# synth-zodiac-scorpio-kbd.net
KiCad netlist of a schematic drawn in EAGLE
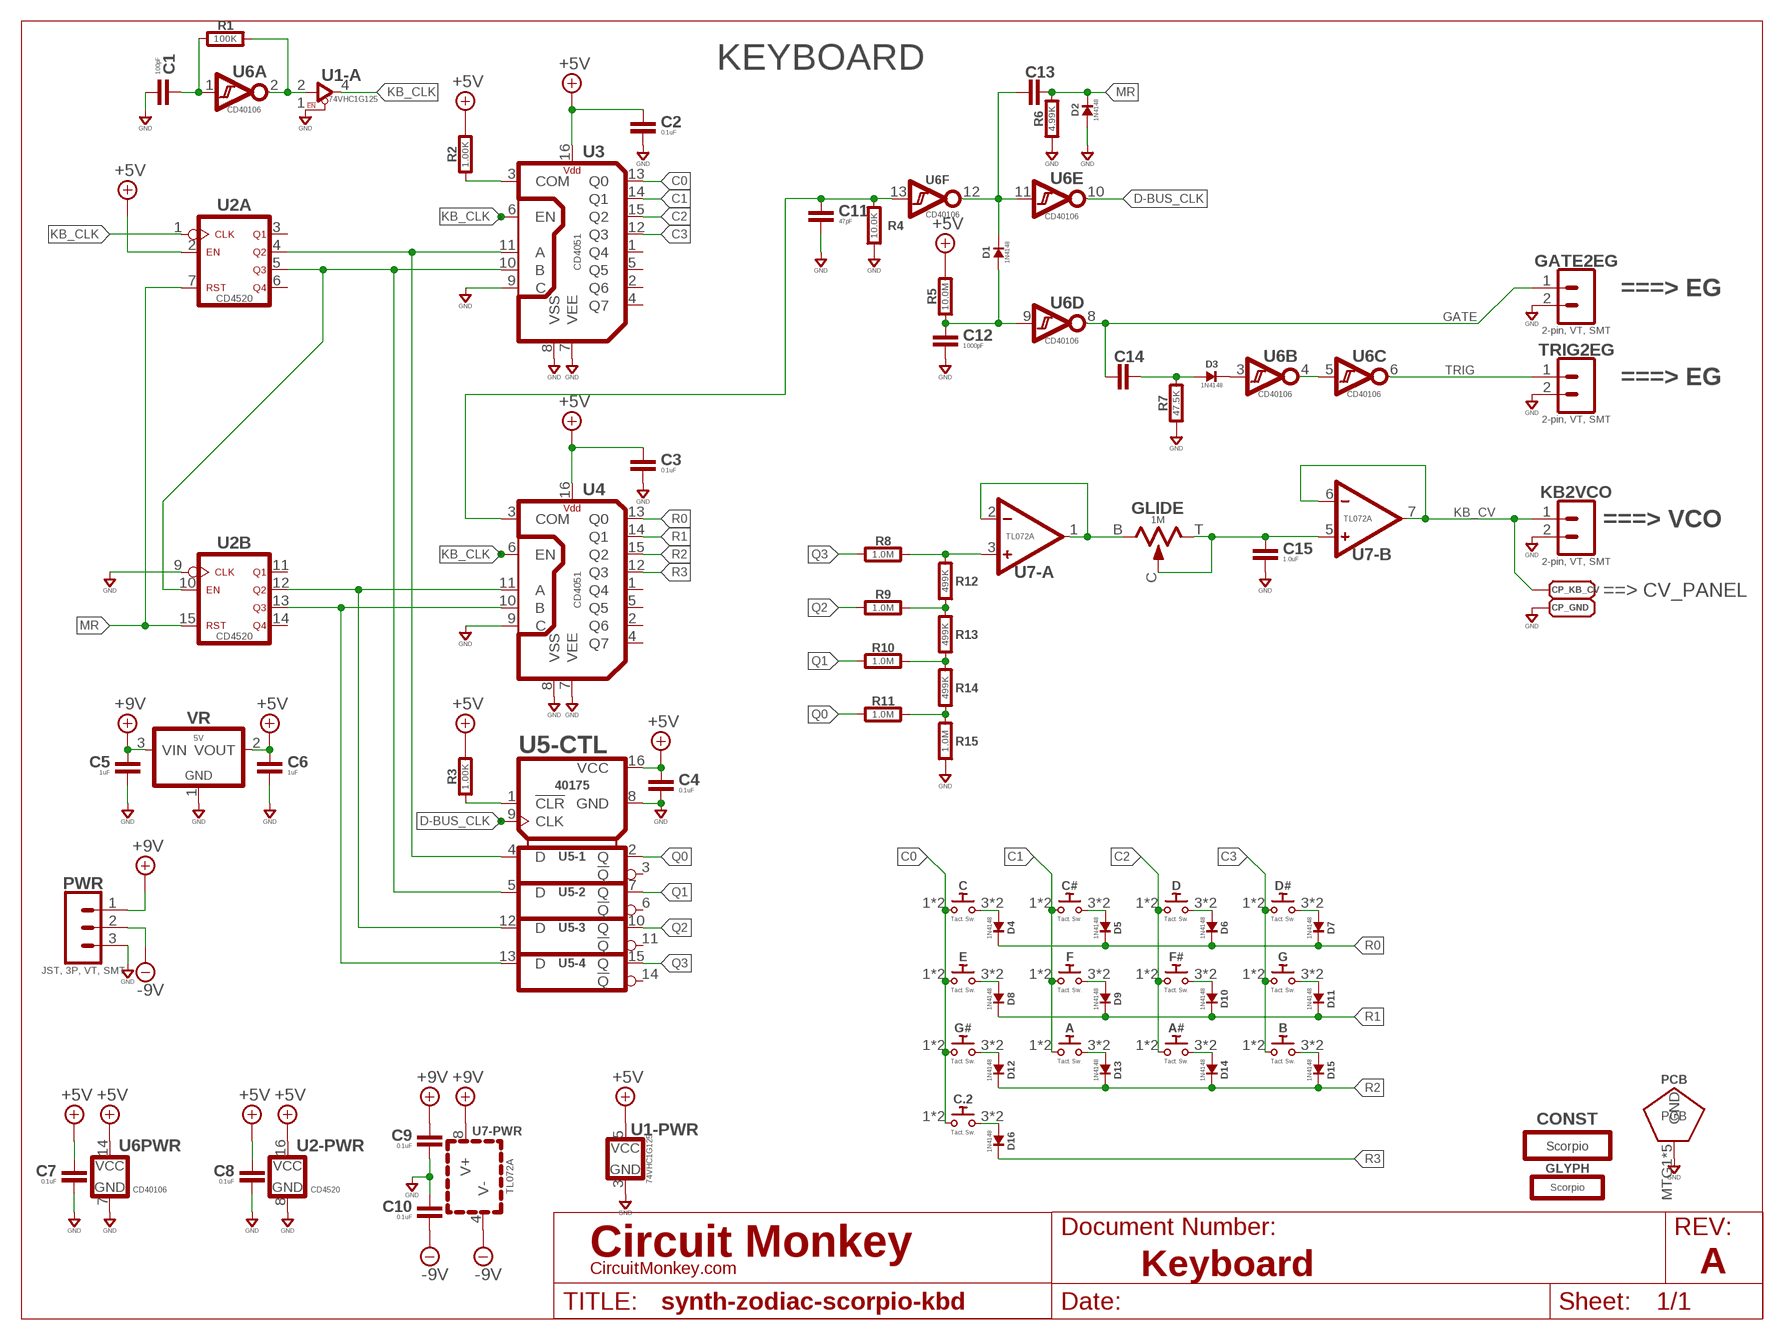
[diagram p0: schematic, sheet 1]

(export (version "E")
  (design (tool "Eeschema 10.0.6"))
  (components
    (comp (ref "A")
      (value "Tact. Sw.")
      (footprint "eagle-import:B3FS")
      (fields (field (name "MFR") "Omron") (field (name "MPN") "B3FS-10*"))
      (libsource (lib "eagle-import") (part "PUSHBTN-MOMB3FS"))
    )
    (comp (ref "A#")
      (value "Tact. Sw.")
      (footprint "eagle-import:B3FS")
      (fields (field (name "MFR") "Omron") (field (name "MPN") "B3FS-10*"))
      (libsource (lib "eagle-import") (part "PUSHBTN-MOMB3FS"))
    )
    (comp (ref "B")
      (value "Tact. Sw.")
      (footprint "eagle-import:B3FS")
      (fields (field (name "MFR") "Omron") (field (name "MPN") "B3FS-10*"))
      (libsource (lib "eagle-import") (part "PUSHBTN-MOMB3FS"))
    )
    (comp (ref "C")
      (value "Tact. Sw.")
      (footprint "eagle-import:B3FS")
      (fields (field (name "MFR") "Omron") (field (name "MPN") "B3FS-10*"))
      (libsource (lib "eagle-import") (part "PUSHBTN-MOMB3FS"))
    )
    (comp (ref "C#")
      (value "Tact. Sw.")
      (footprint "eagle-import:B3FS")
      (fields (field (name "MFR") "Omron") (field (name "MPN") "B3FS-10*"))
      (libsource (lib "eagle-import") (part "PUSHBTN-MOMB3FS"))
    )
    (comp (ref "C.2")
      (value "Tact. Sw.")
      (footprint "eagle-import:B3FS")
      (fields (field (name "MFR") "Omron") (field (name "MPN") "B3FS-10*"))
      (libsource (lib "eagle-import") (part "PUSHBTN-MOMB3FS"))
    )
    (comp (ref "C1")
      (value "100pF")
      (footprint "eagle-import:0603-CAP")
      (libsource (lib "eagle-import") (part "CAPACITOR0603"))
    )
    (comp (ref "C2")
      (value "0.1uF")
      (footprint "eagle-import:0603-CAP")
      (libsource (lib "eagle-import") (part "CAPACITOR0603"))
    )
    (comp (ref "C3")
      (value "0.1uF")
      (footprint "eagle-import:0603-CAP")
      (libsource (lib "eagle-import") (part "CAPACITOR0603"))
    )
    (comp (ref "C4")
      (value "0.1uF")
      (footprint "eagle-import:0603-CAP")
      (libsource (lib "eagle-import") (part "CAPACITOR0603"))
    )
    (comp (ref "C5")
      (value "1uF")
      (footprint "eagle-import:0603-CAP")
      (libsource (lib "eagle-import") (part "CAPACITOR0603"))
    )
    (comp (ref "C6")
      (value "1uF")
      (footprint "eagle-import:0603-CAP")
      (libsource (lib "eagle-import") (part "CAPACITOR0603"))
    )
    (comp (ref "C7")
      (value "0.1uF")
      (footprint "eagle-import:0603-CAP")
      (libsource (lib "eagle-import") (part "CAPACITOR0603"))
    )
    (comp (ref "C8")
      (value "0.1uF")
      (footprint "eagle-import:0603-CAP")
      (libsource (lib "eagle-import") (part "CAPACITOR0603"))
    )
    (comp (ref "C9")
      (value "0.1uF")
      (footprint "eagle-import:0603-CAP")
      (libsource (lib "eagle-import") (part "CAPACITOR0603"))
    )
    (comp (ref "C10")
      (value "0.1uF")
      (footprint "eagle-import:0603-CAP")
      (libsource (lib "eagle-import") (part "CAPACITOR0603"))
    )
    (comp (ref "C11")
      (value "47pF")
      (footprint "eagle-import:0603-CAP")
      (libsource (lib "eagle-import") (part "CAPACITOR0603"))
    )
    (comp (ref "C12")
      (value "1000pF")
      (footprint "eagle-import:0603-CAP")
      (libsource (lib "eagle-import") (part "CAPACITOR0603"))
    )
    (comp (ref "C13")
      (value "220pF")
      (footprint "eagle-import:0603-CAP")
      (libsource (lib "eagle-import") (part "CAPACITOR0603"))
    )
    (comp (ref "C14")
      (value "0.1uF")
      (footprint "eagle-import:0603-CAP")
      (libsource (lib "eagle-import") (part "CAPACITOR0603"))
    )
    (comp (ref "C15")
      (value "1.0uF")
      (footprint "eagle-import:0603-CAP")
      (libsource (lib "eagle-import") (part "CAPACITOR0603"))
    )
    (comp (ref "CONST")
      (value "Scorpio")
      (footprint "eagle-import:SCORPIO-CONST")
      (libsource (lib "eagle-import") (part "CONSTELLATION-SCORPIO"))
    )
    (comp (ref "CP_GND")
      (value "PAD-70X70SMD-070X070")
      (footprint "eagle-import:SMD-070MIL")
      (libsource (lib "eagle-import") (part "PAD-70X70SMD-070X070"))
    )
    (comp (ref "CP_KB_CV")
      (value "PAD-70X70SMD-070X070")
      (footprint "eagle-import:SMD-070MIL")
      (libsource (lib "eagle-import") (part "PAD-70X70SMD-070X070"))
    )
    (comp (ref "D")
      (value "Tact. Sw.")
      (footprint "eagle-import:B3FS")
      (fields (field (name "MFR") "Omron") (field (name "MPN") "B3FS-10*"))
      (libsource (lib "eagle-import") (part "PUSHBTN-MOMB3FS"))
    )
    (comp (ref "D#")
      (value "Tact. Sw.")
      (footprint "eagle-import:B3FS")
      (fields (field (name "MFR") "Omron") (field (name "MPN") "B3FS-10*"))
      (libsource (lib "eagle-import") (part "PUSHBTN-MOMB3FS"))
    )
    (comp (ref "D1")
      (value "1N4148")
      (footprint "eagle-import:SOD-123")
      (fields (field (name "MPN") "1N4148W"))
      (libsource (lib "eagle-import") (part "DIODE-1N4148"))
    )
    (comp (ref "D2")
      (value "1N4148")
      (footprint "eagle-import:SOD-123")
      (fields (field (name "MPN") "1N4148W"))
      (libsource (lib "eagle-import") (part "DIODE-1N4148"))
    )
    (comp (ref "D3")
      (value "1N4148")
      (footprint "eagle-import:SOD-123")
      (fields (field (name "MPN") "1N4148W"))
      (libsource (lib "eagle-import") (part "DIODE-1N4148"))
    )
    (comp (ref "D4")
      (value "1N4148")
      (footprint "eagle-import:SOD-123")
      (fields (field (name "MPN") "1N4148W"))
      (libsource (lib "eagle-import") (part "DIODE-1N4148"))
    )
    (comp (ref "D5")
      (value "1N4148")
      (footprint "eagle-import:SOD-123")
      (fields (field (name "MPN") "1N4148W"))
      (libsource (lib "eagle-import") (part "DIODE-1N4148"))
    )
    (comp (ref "D6")
      (value "1N4148")
      (footprint "eagle-import:SOD-123")
      (fields (field (name "MPN") "1N4148W"))
      (libsource (lib "eagle-import") (part "DIODE-1N4148"))
    )
    (comp (ref "D7")
      (value "1N4148")
      (footprint "eagle-import:SOD-123")
      (fields (field (name "MPN") "1N4148W"))
      (libsource (lib "eagle-import") (part "DIODE-1N4148"))
    )
    (comp (ref "D8")
      (value "1N4148")
      (footprint "eagle-import:SOD-123")
      (fields (field (name "MPN") "1N4148W"))
      (libsource (lib "eagle-import") (part "DIODE-1N4148"))
    )
    (comp (ref "D9")
      (value "1N4148")
      (footprint "eagle-import:SOD-123")
      (fields (field (name "MPN") "1N4148W"))
      (libsource (lib "eagle-import") (part "DIODE-1N4148"))
    )
    (comp (ref "D10")
      (value "1N4148")
      (footprint "eagle-import:SOD-123")
      (fields (field (name "MPN") "1N4148W"))
      (libsource (lib "eagle-import") (part "DIODE-1N4148"))
    )
    (comp (ref "D11")
      (value "1N4148")
      (footprint "eagle-import:SOD-123")
      (fields (field (name "MPN") "1N4148W"))
      (libsource (lib "eagle-import") (part "DIODE-1N4148"))
    )
    (comp (ref "D12")
      (value "1N4148")
      (footprint "eagle-import:SOD-123")
      (fields (field (name "MPN") "1N4148W"))
      (libsource (lib "eagle-import") (part "DIODE-1N4148"))
    )
    (comp (ref "D13")
      (value "1N4148")
      (footprint "eagle-import:SOD-123")
      (fields (field (name "MPN") "1N4148W"))
      (libsource (lib "eagle-import") (part "DIODE-1N4148"))
    )
    (comp (ref "D14")
      (value "1N4148")
      (footprint "eagle-import:SOD-123")
      (fields (field (name "MPN") "1N4148W"))
      (libsource (lib "eagle-import") (part "DIODE-1N4148"))
    )
    (comp (ref "D15")
      (value "1N4148")
      (footprint "eagle-import:SOD-123")
      (fields (field (name "MPN") "1N4148W"))
      (libsource (lib "eagle-import") (part "DIODE-1N4148"))
    )
    (comp (ref "D16")
      (value "1N4148")
      (footprint "eagle-import:SOD-123")
      (fields (field (name "MPN") "1N4148W"))
      (libsource (lib "eagle-import") (part "DIODE-1N4148"))
    )
    (comp (ref "E")
      (value "Tact. Sw.")
      (footprint "eagle-import:B3FS")
      (fields (field (name "MFR") "Omron") (field (name "MPN") "B3FS-10*"))
      (libsource (lib "eagle-import") (part "PUSHBTN-MOMB3FS"))
    )
    (comp (ref "F")
      (value "Tact. Sw.")
      (footprint "eagle-import:B3FS")
      (fields (field (name "MFR") "Omron") (field (name "MPN") "B3FS-10*"))
      (libsource (lib "eagle-import") (part "PUSHBTN-MOMB3FS"))
    )
    (comp (ref "F#")
      (value "Tact. Sw.")
      (footprint "eagle-import:B3FS")
      (fields (field (name "MFR") "Omron") (field (name "MPN") "B3FS-10*"))
      (libsource (lib "eagle-import") (part "PUSHBTN-MOMB3FS"))
    )
    (comp (ref "G")
      (value "Tact. Sw.")
      (footprint "eagle-import:B3FS")
      (fields (field (name "MFR") "Omron") (field (name "MPN") "B3FS-10*"))
      (libsource (lib "eagle-import") (part "PUSHBTN-MOMB3FS"))
    )
    (comp (ref "G#")
      (value "Tact. Sw.")
      (footprint "eagle-import:B3FS")
      (fields (field (name "MFR") "Omron") (field (name "MPN") "B3FS-10*"))
      (libsource (lib "eagle-import") (part "PUSHBTN-MOMB3FS"))
    )
    (comp (ref "GATE2EG")
      (value "2-pin, VT, SMT")
      (footprint "eagle-import:B2B-PH-SM4")
      (fields (field (name "MFR") "JST") (field (name "MPN") "B2B-PH-SM4"))
      (libsource (lib "eagle-import") (part "02PVT-SMT"))
    )
    (comp (ref "GLIDE")
      (value "1M")
      (footprint "eagle-import:POT-RV9110")
      (fields (field (name "MFR") "Tayda") (field (name "MPN") "RV9110NO-OS15A00"))
      (libsource (lib "eagle-import") (part "TRIMPOT9MM_PCB_SHAFT"))
    )
    (comp (ref "GLYPH")
      (value "Scorpio")
      (footprint "eagle-import:SCORPIO-GLYPH")
      (libsource (lib "eagle-import") (part "GLYPH-SCORPIO"))
    )
    (comp (ref "KB2VCO")
      (value "2-pin, VT, SMT")
      (footprint "eagle-import:B2B-PH-SM4")
      (fields (field (name "MFR") "JST") (field (name "MPN") "B2B-PH-SM4"))
      (libsource (lib "eagle-import") (part "02PVT-SMT"))
    )
    (comp (ref "PCB")
      (value "PCB FAB")
      (footprint "eagle-import:PENTAGON-40MM-RAD")
      (libsource (lib "eagle-import") (part "PENTAGON-40R"))
    )
    (comp (ref "PWR")
      (value "JST, 3P, VT, SMT")
      (footprint "eagle-import:B3B-PH-SM4")
      (fields (field (name "MFR") "JST") (field (name "MPN") "B3B-PH-SM4"))
      (libsource (lib "eagle-import") (part "03P-VT-SMT"))
    )
    (comp (ref "R1")
      (value "100K")
      (footprint "eagle-import:0603-RES")
      (libsource (lib "eagle-import") (part "RESISTOR0603"))
    )
    (comp (ref "R2")
      (value "1.00K")
      (footprint "eagle-import:0603-RES")
      (libsource (lib "eagle-import") (part "RESISTOR0603"))
    )
    (comp (ref "R3")
      (value "1.00K")
      (footprint "eagle-import:0603-RES")
      (libsource (lib "eagle-import") (part "RESISTOR0603"))
    )
    (comp (ref "R4")
      (value "10.0K")
      (footprint "eagle-import:0603-RES")
      (libsource (lib "eagle-import") (part "RESISTOR0603"))
    )
    (comp (ref "R5")
      (value "10.0M")
      (footprint "eagle-import:0603-RES")
      (libsource (lib "eagle-import") (part "RESISTOR0603"))
    )
    (comp (ref "R6")
      (value "4.99K")
      (footprint "eagle-import:0603-RES")
      (libsource (lib "eagle-import") (part "RESISTOR0603"))
    )
    (comp (ref "R7")
      (value "47.5K")
      (footprint "eagle-import:0603-RES")
      (libsource (lib "eagle-import") (part "RESISTOR0603"))
    )
    (comp (ref "R8")
      (value "1.0M")
      (footprint "eagle-import:0603-RES")
      (libsource (lib "eagle-import") (part "RESISTOR0603"))
    )
    (comp (ref "R9")
      (value "1.0M")
      (footprint "eagle-import:0603-RES")
      (libsource (lib "eagle-import") (part "RESISTOR0603"))
    )
    (comp (ref "R10")
      (value "1.0M")
      (footprint "eagle-import:0603-RES")
      (libsource (lib "eagle-import") (part "RESISTOR0603"))
    )
    (comp (ref "R11")
      (value "1.0M")
      (footprint "eagle-import:0603-RES")
      (libsource (lib "eagle-import") (part "RESISTOR0603"))
    )
    (comp (ref "R12")
      (value "499K")
      (footprint "eagle-import:0603-RES")
      (libsource (lib "eagle-import") (part "RESISTOR0603"))
    )
    (comp (ref "R13")
      (value "499K")
      (footprint "eagle-import:0603-RES")
      (libsource (lib "eagle-import") (part "RESISTOR0603"))
    )
    (comp (ref "R14")
      (value "499K")
      (footprint "eagle-import:0603-RES")
      (libsource (lib "eagle-import") (part "RESISTOR0603"))
    )
    (comp (ref "R15")
      (value "1.0M")
      (footprint "eagle-import:0603-RES")
      (libsource (lib "eagle-import") (part "RESISTOR0603"))
    )
    (comp (ref "TRIG2EG")
      (value "2-pin, VT, SMT")
      (footprint "eagle-import:B2B-PH-SM4")
      (fields (field (name "MFR") "JST") (field (name "MPN") "B2B-PH-SM4"))
      (libsource (lib "eagle-import") (part "02PVT-SMT"))
    )
    (comp (ref "U1")
      (value "74VHC1G125")
      (footprint "eagle-import:TSOP-5")
      (fields (field (name "MFR") "ON Semi") (field (name "MPN") "MC74VHC1G125P5TG"))
      (libsource (lib "eagle-import") (part "74VHC1G125CMOS-SOT553"))
    )
    (comp (ref "U2")
      (value "CD4520")
      (footprint "eagle-import:SO16")
      (fields (field (name "MFR") "TI") (field (name "MPN") "CD4520BM96"))
      (libsource (lib "eagle-import") (part "CD4520"))
    )
    (comp (ref "U3")
      (value "CD4051")
      (footprint "eagle-import:SO16")
      (fields (field (name "MFR") "TI") (field (name "MPN") "CD4051BM"))
      (libsource (lib "eagle-import") (part "CD4051SO-D"))
    )
    (comp (ref "U4")
      (value "CD4051")
      (footprint "eagle-import:SO16")
      (fields (field (name "MFR") "TI") (field (name "MPN") "CD4051BM"))
      (libsource (lib "eagle-import") (part "CD4051SO-D"))
    )
    (comp (ref "U5")
      (value "40175")
      (footprint "eagle-import:SO16")
      (fields (field (name "MFR") "TI") (field (name "MPN") "CD40175BM"))
      (libsource (lib "eagle-import") (part "CD40175SMT-D-TYPE"))
    )
    (comp (ref "U6")
      (value "CD40106")
      (footprint "eagle-import:SOP14")
      (fields (field (name "MFR") "TI") (field (name "MPN") "CD40106BM"))
      (libsource (lib "eagle-import") (part "CD40106-SOP14"))
    )
    (comp (ref "U7")
      (value "TL072A")
      (footprint "eagle-import:SOP08")
      (fields (field (name "MFR") "ST"))
      (libsource (lib "eagle-import") (part "DUALTL072A"))
    )
    (comp (ref "VR")
      (value "5V")
      (footprint "eagle-import:SOT-23")
      (fields (field (name "MFR") "Diodes, Inc.") (field (name "MPN") "AP7387-50SA"))
      (libsource (lib "eagle-import") (part "LDO-3P--5V-SOT23"))
    )
  )
  (nets
    (net (code "1") (name "+5V") (class "Default")
      (node (ref "C2") (pin "1") (pinfunction "1_1") (pintype "passive"))
      (node (ref "C3") (pin "1") (pinfunction "1_1") (pintype "passive"))
      (node (ref "C4") (pin "1") (pinfunction "1_1") (pintype "passive"))
      (node (ref "C6") (pin "1") (pinfunction "1_1") (pintype "passive"))
      (node (ref "C7") (pin "1") (pinfunction "1_1") (pintype "passive"))
      (node (ref "C8") (pin "1") (pinfunction "1_1") (pintype "passive"))
      (node (ref "R2") (pin "2") (pinfunction "2_2") (pintype "passive"))
      (node (ref "R3") (pin "2") (pinfunction "2_2") (pintype "passive"))
      (node (ref "R5") (pin "2") (pinfunction "2_2") (pintype "passive"))
      (node (ref "U1") (pin "5") (pinfunction "VCC_5") (pintype "power_in"))
      (node (ref "U2") (pin "16") (pinfunction "VCC_16") (pintype "power_in"))
      (node (ref "U2") (pin "2") (pinfunction "EN_2") (pintype "input"))
      (node (ref "U3") (pin "16") (pinfunction "VDD_16") (pintype "power_in"))
      (node (ref "U4") (pin "16") (pinfunction "VDD_16") (pintype "power_in"))
      (node (ref "U5") (pin "16") (pinfunction "VCC_16") (pintype "power_in"))
      (node (ref "U6") (pin "14") (pinfunction "VCC_14") (pintype "power_in"))
      (node (ref "VR") (pin "2") (pinfunction "VOUT_2") (pintype "power_in"))
    )
    (net (code "2") (name "+9V") (class "Default")
      (node (ref "C5") (pin "1") (pinfunction "1_1") (pintype "passive"))
      (node (ref "C9") (pin "1") (pinfunction "1_1") (pintype "passive"))
      (node (ref "PWR") (pin "1") (pinfunction "1_1") (pintype "passive"))
      (node (ref "U7") (pin "8") (pinfunction "V+_8") (pintype "power_in"))
      (node (ref "VR") (pin "3") (pinfunction "VIN_3") (pintype "power_in"))
    )
    (net (code "3") (name "-9V") (class "Default")
      (node (ref "C10") (pin "2") (pinfunction "2_2") (pintype "passive"))
      (node (ref "PWR") (pin "2") (pinfunction "2_2") (pintype "passive"))
      (node (ref "U7") (pin "4") (pinfunction "V-_4") (pintype "power_in"))
    )
    (net (code "4") (name "/GATE") (class "Default")
      (node (ref "C14") (pin "1") (pinfunction "1_1") (pintype "passive"))
      (node (ref "GATE2EG") (pin "1") (pinfunction "1_1") (pintype "passive"))
      (node (ref "U6") (pin "8") (pinfunction "Y_8") (pintype "bidirectional"))
    )
    (net (code "5") (name "/KB_CV") (class "Default")
      (node (ref "CP_KB_CV") (pin "1") (pinfunction "PAD_1") (pintype "bidirectional"))
      (node (ref "KB2VCO") (pin "1") (pinfunction "1_1") (pintype "passive"))
      (node (ref "U7") (pin "6") (pinfunction "-_6") (pintype "input"))
      (node (ref "U7") (pin "7") (pinfunction "OUT_7") (pintype "output"))
    )
    (net (code "6") (name "/TRIG") (class "Default")
      (node (ref "TRIG2EG") (pin "1") (pinfunction "1_1") (pintype "passive"))
      (node (ref "U6") (pin "6") (pinfunction "Y_6") (pintype "bidirectional"))
    )
    (net (code "7") (name "C0") (class "Default")
      (node (ref "C") (pin "1") (pinfunction "1_1") (pintype "passive"))
      (node (ref "C") (pin "2") (pinfunction "1_2") (pintype "passive"))
      (node (ref "C.2") (pin "1") (pinfunction "1_1") (pintype "passive"))
      (node (ref "C.2") (pin "2") (pinfunction "1_2") (pintype "passive"))
      (node (ref "E") (pin "1") (pinfunction "1_1") (pintype "passive"))
      (node (ref "E") (pin "2") (pinfunction "1_2") (pintype "passive"))
      (node (ref "G#") (pin "1") (pinfunction "1_1") (pintype "passive"))
      (node (ref "G#") (pin "2") (pinfunction "1_2") (pintype "passive"))
      (node (ref "U3") (pin "13") (pinfunction "Q0_13") (pintype "bidirectional"))
    )
    (net (code "8") (name "C1") (class "Default")
      (node (ref "A") (pin "1") (pinfunction "1_1") (pintype "passive"))
      (node (ref "A") (pin "2") (pinfunction "1_2") (pintype "passive"))
      (node (ref "C#") (pin "1") (pinfunction "1_1") (pintype "passive"))
      (node (ref "C#") (pin "2") (pinfunction "1_2") (pintype "passive"))
      (node (ref "F") (pin "1") (pinfunction "1_1") (pintype "passive"))
      (node (ref "F") (pin "2") (pinfunction "1_2") (pintype "passive"))
      (node (ref "U3") (pin "14") (pinfunction "Q1_14") (pintype "bidirectional"))
    )
    (net (code "9") (name "C2") (class "Default")
      (node (ref "A#") (pin "1") (pinfunction "1_1") (pintype "passive"))
      (node (ref "A#") (pin "2") (pinfunction "1_2") (pintype "passive"))
      (node (ref "D") (pin "1") (pinfunction "1_1") (pintype "passive"))
      (node (ref "D") (pin "2") (pinfunction "1_2") (pintype "passive"))
      (node (ref "F#") (pin "1") (pinfunction "1_1") (pintype "passive"))
      (node (ref "F#") (pin "2") (pinfunction "1_2") (pintype "passive"))
      (node (ref "U3") (pin "15") (pinfunction "Q2_15") (pintype "bidirectional"))
    )
    (net (code "10") (name "C3") (class "Default")
      (node (ref "B") (pin "1") (pinfunction "1_1") (pintype "passive"))
      (node (ref "B") (pin "2") (pinfunction "1_2") (pintype "passive"))
      (node (ref "D#") (pin "1") (pinfunction "1_1") (pintype "passive"))
      (node (ref "D#") (pin "2") (pinfunction "1_2") (pintype "passive"))
      (node (ref "G") (pin "1") (pinfunction "1_1") (pintype "passive"))
      (node (ref "G") (pin "2") (pinfunction "1_2") (pintype "passive"))
      (node (ref "U3") (pin "12") (pinfunction "Q3_12") (pintype "bidirectional"))
    )
    (net (code "11") (name "D-BUS_CLK") (class "Default")
      (node (ref "U5") (pin "9") (pinfunction "CLK_9") (pintype "input"))
      (node (ref "U6") (pin "10") (pinfunction "Y_10") (pintype "bidirectional"))
    )
    (net (code "12") (name "GND") (class "Default")
      (node (ref "C1") (pin "2") (pinfunction "2_2") (pintype "passive"))
      (node (ref "C10") (pin "1") (pinfunction "1_1") (pintype "passive"))
      (node (ref "C11") (pin "2") (pinfunction "2_2") (pintype "passive"))
      (node (ref "C12") (pin "2") (pinfunction "2_2") (pintype "passive"))
      (node (ref "C15") (pin "2") (pinfunction "2_2") (pintype "passive"))
      (node (ref "C2") (pin "2") (pinfunction "2_2") (pintype "passive"))
      (node (ref "C3") (pin "2") (pinfunction "2_2") (pintype "passive"))
      (node (ref "C4") (pin "2") (pinfunction "2_2") (pintype "passive"))
      (node (ref "C5") (pin "2") (pinfunction "2_2") (pintype "passive"))
      (node (ref "C6") (pin "2") (pinfunction "2_2") (pintype "passive"))
      (node (ref "C7") (pin "2") (pinfunction "2_2") (pintype "passive"))
      (node (ref "C8") (pin "2") (pinfunction "2_2") (pintype "passive"))
      (node (ref "C9") (pin "2") (pinfunction "2_2") (pintype "passive"))
      (node (ref "CP_GND") (pin "1") (pinfunction "PAD_1") (pintype "bidirectional"))
      (node (ref "D2") (pin "A") (pinfunction "A_A") (pintype "passive"))
      (node (ref "GATE2EG") (pin "2") (pinfunction "2_2") (pintype "passive"))
      (node (ref "KB2VCO") (pin "2") (pinfunction "2_2") (pintype "passive"))
      (node (ref "PCB") (pin "MTG1") (pinfunction "GND_MTG1") (pintype "bidirectional"))
      (node (ref "PCB") (pin "MTG2") (pinfunction "GND_MTG2") (pintype "bidirectional"))
      (node (ref "PCB") (pin "MTG3") (pinfunction "GND_MTG3") (pintype "bidirectional"))
      (node (ref "PCB") (pin "MTG4") (pinfunction "GND_MTG4") (pintype "bidirectional"))
      (node (ref "PCB") (pin "MTG5") (pinfunction "GND_MTG5") (pintype "bidirectional"))
      (node (ref "PWR") (pin "3") (pinfunction "3_3") (pintype "passive"))
      (node (ref "R15") (pin "1") (pinfunction "1_1") (pintype "passive"))
      (node (ref "R4") (pin "1") (pinfunction "1_1") (pintype "passive"))
      (node (ref "R6") (pin "1") (pinfunction "1_1") (pintype "passive"))
      (node (ref "R7") (pin "1") (pinfunction "1_1") (pintype "passive"))
      (node (ref "TRIG2EG") (pin "2") (pinfunction "2_2") (pintype "passive"))
      (node (ref "U1") (pin "1") (pinfunction "~{EN}_1") (pintype "input"))
      (node (ref "U1") (pin "3") (pinfunction "GND_3") (pintype "power_in"))
      (node (ref "U2") (pin "8") (pinfunction "GND_8") (pintype "power_in"))
      (node (ref "U2") (pin "9") (pinfunction "~{CLK}_9") (pintype "input"))
      (node (ref "U3") (pin "7") (pinfunction "VEE_7") (pintype "power_in"))
      (node (ref "U3") (pin "8") (pinfunction "VSS_8") (pintype "power_in"))
      (node (ref "U3") (pin "9") (pinfunction "C_9") (pintype "input"))
      (node (ref "U4") (pin "7") (pinfunction "VEE_7") (pintype "power_in"))
      (node (ref "U4") (pin "8") (pinfunction "VSS_8") (pintype "power_in"))
      (node (ref "U4") (pin "9") (pinfunction "C_9") (pintype "input"))
      (node (ref "U5") (pin "8") (pinfunction "GND_8") (pintype "power_in"))
      (node (ref "U6") (pin "7") (pinfunction "GND_7") (pintype "power_in"))
      (node (ref "VR") (pin "1") (pinfunction "GND_1") (pintype "power_in"))
    )
    (net (code "13") (name "KB_CLK") (class "Default")
      (node (ref "U1") (pin "4") (pinfunction "Y_4") (pintype "output"))
      (node (ref "U2") (pin "1") (pinfunction "~{CLK}_1") (pintype "input"))
      (node (ref "U3") (pin "6") (pinfunction "EN_6") (pintype "input"))
      (node (ref "U4") (pin "6") (pinfunction "EN_6") (pintype "input"))
    )
    (net (code "14") (name "MR") (class "Default")
      (node (ref "C13") (pin "2") (pinfunction "2_2") (pintype "passive"))
      (node (ref "D2") (pin "K") (pinfunction "K_K") (pintype "passive"))
      (node (ref "R6") (pin "2") (pinfunction "2_2") (pintype "passive"))
      (node (ref "U2") (pin "15") (pinfunction "RST_15") (pintype "input"))
      (node (ref "U2") (pin "7") (pinfunction "RST_7") (pintype "input"))
    )
    (net (code "15") (name "Net-(A#-2-Pad3)") (class "Default")
      (node (ref "A#") (pin "3") (pinfunction "2_3") (pintype "passive"))
      (node (ref "A#") (pin "4") (pinfunction "2_4") (pintype "passive"))
      (node (ref "D14") (pin "A") (pinfunction "A_A") (pintype "passive"))
    )
    (net (code "16") (name "Net-(A-2-Pad3)") (class "Default")
      (node (ref "A") (pin "3") (pinfunction "2_3") (pintype "passive"))
      (node (ref "A") (pin "4") (pinfunction "2_4") (pintype "passive"))
      (node (ref "D13") (pin "A") (pinfunction "A_A") (pintype "passive"))
    )
    (net (code "17") (name "Net-(B-2-Pad3)") (class "Default")
      (node (ref "B") (pin "3") (pinfunction "2_3") (pintype "passive"))
      (node (ref "B") (pin "4") (pinfunction "2_4") (pintype "passive"))
      (node (ref "D15") (pin "A") (pinfunction "A_A") (pintype "passive"))
    )
    (net (code "18") (name "Net-(C#-2-Pad3)") (class "Default")
      (node (ref "C#") (pin "3") (pinfunction "2_3") (pintype "passive"))
      (node (ref "C#") (pin "4") (pinfunction "2_4") (pintype "passive"))
      (node (ref "D5") (pin "A") (pinfunction "A_A") (pintype "passive"))
    )
    (net (code "19") (name "Net-(C-2-Pad3)") (class "Default")
      (node (ref "C") (pin "3") (pinfunction "2_3") (pintype "passive"))
      (node (ref "C") (pin "4") (pinfunction "2_4") (pintype "passive"))
      (node (ref "D4") (pin "A") (pinfunction "A_A") (pintype "passive"))
    )
    (net (code "20") (name "Net-(C.2-2-Pad3)") (class "Default")
      (node (ref "C.2") (pin "3") (pinfunction "2_3") (pintype "passive"))
      (node (ref "C.2") (pin "4") (pinfunction "2_4") (pintype "passive"))
      (node (ref "D16") (pin "A") (pinfunction "A_A") (pintype "passive"))
    )
    (net (code "21") (name "Net-(C14-Pad2)") (class "Default")
      (node (ref "C14") (pin "2") (pinfunction "2_2") (pintype "passive"))
      (node (ref "D3") (pin "A") (pinfunction "A_A") (pintype "passive"))
      (node (ref "R7") (pin "2") (pinfunction "2_2") (pintype "passive"))
    )
    (net (code "22") (name "Net-(D#-2-Pad3)") (class "Default")
      (node (ref "D#") (pin "3") (pinfunction "2_3") (pintype "passive"))
      (node (ref "D#") (pin "4") (pinfunction "2_4") (pintype "passive"))
      (node (ref "D7") (pin "A") (pinfunction "A_A") (pintype "passive"))
    )
    (net (code "23") (name "Net-(D-2-Pad3)") (class "Default")
      (node (ref "D") (pin "3") (pinfunction "2_3") (pintype "passive"))
      (node (ref "D") (pin "4") (pinfunction "2_4") (pintype "passive"))
      (node (ref "D6") (pin "A") (pinfunction "A_A") (pintype "passive"))
    )
    (net (code "24") (name "Net-(D8-PadA)") (class "Default")
      (node (ref "D8") (pin "A") (pinfunction "A_A") (pintype "passive"))
      (node (ref "E") (pin "3") (pinfunction "2_3") (pintype "passive"))
      (node (ref "E") (pin "4") (pinfunction "2_4") (pintype "passive"))
    )
    (net (code "25") (name "Net-(D9-PadA)") (class "Default")
      (node (ref "D9") (pin "A") (pinfunction "A_A") (pintype "passive"))
      (node (ref "F") (pin "3") (pinfunction "2_3") (pintype "passive"))
      (node (ref "F") (pin "4") (pinfunction "2_4") (pintype "passive"))
    )
    (net (code "26") (name "Net-(D10-PadA)") (class "Default")
      (node (ref "D10") (pin "A") (pinfunction "A_A") (pintype "passive"))
      (node (ref "F#") (pin "3") (pinfunction "2_3") (pintype "passive"))
      (node (ref "F#") (pin "4") (pinfunction "2_4") (pintype "passive"))
    )
    (net (code "27") (name "Net-(D11-PadA)") (class "Default")
      (node (ref "D11") (pin "A") (pinfunction "A_A") (pintype "passive"))
      (node (ref "G") (pin "3") (pinfunction "2_3") (pintype "passive"))
      (node (ref "G") (pin "4") (pinfunction "2_4") (pintype "passive"))
    )
    (net (code "28") (name "Net-(D12-PadA)") (class "Default")
      (node (ref "D12") (pin "A") (pinfunction "A_A") (pintype "passive"))
      (node (ref "G#") (pin "3") (pinfunction "2_3") (pintype "passive"))
      (node (ref "G#") (pin "4") (pinfunction "2_4") (pintype "passive"))
    )
    (net (code "29") (name "Net-(GLIDE-1)") (class "Default")
      (node (ref "GLIDE") (pin "B") (pinfunction "1_B") (pintype "passive"))
      (node (ref "U7") (pin "1") (pinfunction "OUT_1") (pintype "output"))
      (node (ref "U7") (pin "2") (pinfunction "-_2") (pintype "input"))
    )
    (net (code "30") (name "Net-(GLIDE-2)") (class "Default")
      (node (ref "C15") (pin "1") (pinfunction "1_1") (pintype "passive"))
      (node (ref "GLIDE") (pin "C") (pinfunction "2_C") (pintype "passive"))
      (node (ref "GLIDE") (pin "T") (pinfunction "3_T") (pintype "passive"))
      (node (ref "U7") (pin "5") (pinfunction "+_5") (pintype "input"))
    )
    (net (code "31") (name "Net-(R10-Pad2)") (class "Default")
      (node (ref "R10") (pin "2") (pinfunction "2_2") (pintype "passive"))
      (node (ref "R13") (pin "1") (pinfunction "1_1") (pintype "passive"))
      (node (ref "R14") (pin "2") (pinfunction "2_2") (pintype "passive"))
    )
    (net (code "32") (name "Net-(R11-Pad2)") (class "Default")
      (node (ref "R11") (pin "2") (pinfunction "2_2") (pintype "passive"))
      (node (ref "R14") (pin "1") (pinfunction "1_1") (pintype "passive"))
      (node (ref "R15") (pin "2") (pinfunction "2_2") (pintype "passive"))
    )
    (net (code "33") (name "Net-(R12-Pad1)") (class "Default")
      (node (ref "R12") (pin "1") (pinfunction "1_1") (pintype "passive"))
      (node (ref "R13") (pin "2") (pinfunction "2_2") (pintype "passive"))
      (node (ref "R9") (pin "2") (pinfunction "2_2") (pintype "passive"))
    )
    (net (code "34") (name "Net-(U1A-A)") (class "Default")
      (node (ref "R1") (pin "2") (pinfunction "2_2") (pintype "passive"))
      (node (ref "U1") (pin "2") (pinfunction "A_2") (pintype "input"))
      (node (ref "U6") (pin "2") (pinfunction "Y_2") (pintype "bidirectional"))
    )
    (net (code "35") (name "Net-(U2B-Q2)") (class "Default")
      (node (ref "U2") (pin "4") (pinfunction "Q2_4") (pintype "output"))
      (node (ref "U3") (pin "11") (pinfunction "A_11") (pintype "input"))
      (node (ref "U5") (pin "4") (pinfunction "D_4") (pintype "input"))
    )
    (net (code "36") (name "Net-(U2B-Q3)") (class "Default")
      (node (ref "U2") (pin "10") (pinfunction "EN_10") (pintype "input"))
      (node (ref "U2") (pin "5") (pinfunction "Q3_5") (pintype "output"))
      (node (ref "U3") (pin "10") (pinfunction "B_10") (pintype "input"))
      (node (ref "U5") (pin "5") (pinfunction "D_5") (pintype "input"))
    )
    (net (code "37") (name "Net-(U2C-Q2)") (class "Default")
      (node (ref "U2") (pin "12") (pinfunction "Q2_12") (pintype "output"))
      (node (ref "U4") (pin "11") (pinfunction "A_11") (pintype "input"))
      (node (ref "U5") (pin "12") (pinfunction "D_12") (pintype "input"))
    )
    (net (code "38") (name "Net-(U2C-Q3)") (class "Default")
      (node (ref "U2") (pin "13") (pinfunction "Q3_13") (pintype "output"))
      (node (ref "U4") (pin "10") (pinfunction "B_10") (pintype "input"))
      (node (ref "U5") (pin "13") (pinfunction "D_13") (pintype "input"))
    )
    (net (code "39") (name "Net-(U3-COM)") (class "Default")
      (node (ref "R2") (pin "1") (pinfunction "1_1") (pintype "passive"))
      (node (ref "U3") (pin "3") (pinfunction "COM_3") (pintype "bidirectional"))
    )
    (net (code "40") (name "Net-(U4-COM)") (class "Default")
      (node (ref "C11") (pin "1") (pinfunction "1_1") (pintype "passive"))
      (node (ref "R4") (pin "2") (pinfunction "2_2") (pintype "passive"))
      (node (ref "U4") (pin "3") (pinfunction "COM_3") (pintype "bidirectional"))
      (node (ref "U6") (pin "13") (pinfunction "A_13") (pintype "bidirectional"))
    )
    (net (code "41") (name "Net-(U5E-~{CLR})") (class "Default")
      (node (ref "R3") (pin "1") (pinfunction "1_1") (pintype "passive"))
      (node (ref "U5") (pin "1") (pinfunction "~{CLR}_1") (pintype "input"))
    )
    (net (code "42") (name "Net-(U6A-A)") (class "Default")
      (node (ref "C1") (pin "1") (pinfunction "1_1") (pintype "passive"))
      (node (ref "R1") (pin "1") (pinfunction "1_1") (pintype "passive"))
      (node (ref "U6") (pin "1") (pinfunction "A_1") (pintype "bidirectional"))
    )
    (net (code "43") (name "Net-(U6B-A)") (class "Default")
      (node (ref "D3") (pin "K") (pinfunction "K_K") (pintype "passive"))
      (node (ref "U6") (pin "3") (pinfunction "A_3") (pintype "bidirectional"))
    )
    (net (code "44") (name "Net-(U6B-Y)") (class "Default")
      (node (ref "U6") (pin "4") (pinfunction "Y_4") (pintype "bidirectional"))
      (node (ref "U6") (pin "5") (pinfunction "A_5") (pintype "bidirectional"))
    )
    (net (code "45") (name "Net-(U6D-A)") (class "Default")
      (node (ref "C12") (pin "1") (pinfunction "1_1") (pintype "passive"))
      (node (ref "D1") (pin "A") (pinfunction "A_A") (pintype "passive"))
      (node (ref "R5") (pin "1") (pinfunction "1_1") (pintype "passive"))
      (node (ref "U6") (pin "9") (pinfunction "A_9") (pintype "bidirectional"))
    )
    (net (code "46") (name "Net-(U6E-A)") (class "Default")
      (node (ref "C13") (pin "1") (pinfunction "1_1") (pintype "passive"))
      (node (ref "D1") (pin "K") (pinfunction "K_K") (pintype "passive"))
      (node (ref "U6") (pin "11") (pinfunction "A_11") (pintype "bidirectional"))
      (node (ref "U6") (pin "12") (pinfunction "Y_12") (pintype "bidirectional"))
    )
    (net (code "47") (name "Net-(U7A-+)") (class "Default")
      (node (ref "R12") (pin "2") (pinfunction "2_2") (pintype "passive"))
      (node (ref "R8") (pin "2") (pinfunction "2_2") (pintype "passive"))
      (node (ref "U7") (pin "3") (pinfunction "+_3") (pintype "input"))
    )
    (net (code "48") (name "Q0") (class "Default")
      (node (ref "R11") (pin "1") (pinfunction "1_1") (pintype "passive"))
      (node (ref "U5") (pin "2") (pinfunction "Q_2") (pintype "output"))
    )
    (net (code "49") (name "Q1") (class "Default")
      (node (ref "R10") (pin "1") (pinfunction "1_1") (pintype "passive"))
      (node (ref "U5") (pin "7") (pinfunction "Q_7") (pintype "output"))
    )
    (net (code "50") (name "Q2") (class "Default")
      (node (ref "R9") (pin "1") (pinfunction "1_1") (pintype "passive"))
      (node (ref "U5") (pin "10") (pinfunction "Q_10") (pintype "output"))
    )
    (net (code "51") (name "Q3") (class "Default")
      (node (ref "R8") (pin "1") (pinfunction "1_1") (pintype "passive"))
      (node (ref "U5") (pin "15") (pinfunction "Q_15") (pintype "output"))
    )
    (net (code "52") (name "R0") (class "Default")
      (node (ref "D4") (pin "K") (pinfunction "K_K") (pintype "passive"))
      (node (ref "D5") (pin "K") (pinfunction "K_K") (pintype "passive"))
      (node (ref "D6") (pin "K") (pinfunction "K_K") (pintype "passive"))
      (node (ref "D7") (pin "K") (pinfunction "K_K") (pintype "passive"))
      (node (ref "U4") (pin "13") (pinfunction "Q0_13") (pintype "bidirectional"))
    )
    (net (code "53") (name "R1") (class "Default")
      (node (ref "D10") (pin "K") (pinfunction "K_K") (pintype "passive"))
      (node (ref "D11") (pin "K") (pinfunction "K_K") (pintype "passive"))
      (node (ref "D8") (pin "K") (pinfunction "K_K") (pintype "passive"))
      (node (ref "D9") (pin "K") (pinfunction "K_K") (pintype "passive"))
      (node (ref "U4") (pin "14") (pinfunction "Q1_14") (pintype "bidirectional"))
    )
    (net (code "54") (name "R2") (class "Default")
      (node (ref "D12") (pin "K") (pinfunction "K_K") (pintype "passive"))
      (node (ref "D13") (pin "K") (pinfunction "K_K") (pintype "passive"))
      (node (ref "D14") (pin "K") (pinfunction "K_K") (pintype "passive"))
      (node (ref "D15") (pin "K") (pinfunction "K_K") (pintype "passive"))
      (node (ref "U4") (pin "15") (pinfunction "Q2_15") (pintype "bidirectional"))
    )
    (net (code "55") (name "R3") (class "Default")
      (node (ref "D16") (pin "K") (pinfunction "K_K") (pintype "passive"))
      (node (ref "U4") (pin "12") (pinfunction "Q3_12") (pintype "bidirectional"))
    )
    (net (code "56") (name "unconnected-(U2B-Q1-Pad3)") (class "Default")
      (node (ref "U2") (pin "3") (pinfunction "Q1_3") (pintype "output"))
    )
    (net (code "57") (name "unconnected-(U2B-Q4-Pad6)") (class "Default")
      (node (ref "U2") (pin "6") (pinfunction "Q4_6") (pintype "output"))
    )
    (net (code "58") (name "unconnected-(U2C-Q1-Pad11)") (class "Default")
      (node (ref "U2") (pin "11") (pinfunction "Q1_11") (pintype "output"))
    )
    (net (code "59") (name "unconnected-(U2C-Q4-Pad14)") (class "Default")
      (node (ref "U2") (pin "14") (pinfunction "Q4_14") (pintype "output"))
    )
    (net (code "60") (name "unconnected-(U3-Q4-Pad1)") (class "Default")
      (node (ref "U3") (pin "1") (pinfunction "Q4_1") (pintype "bidirectional"))
    )
    (net (code "61") (name "unconnected-(U3-Q5-Pad5)") (class "Default")
      (node (ref "U3") (pin "5") (pinfunction "Q5_5") (pintype "bidirectional"))
    )
    (net (code "62") (name "unconnected-(U3-Q6-Pad2)") (class "Default")
      (node (ref "U3") (pin "2") (pinfunction "Q6_2") (pintype "bidirectional"))
    )
    (net (code "63") (name "unconnected-(U3-Q7-Pad4)") (class "Default")
      (node (ref "U3") (pin "4") (pinfunction "Q7_4") (pintype "bidirectional"))
    )
    (net (code "64") (name "unconnected-(U4-Q4-Pad1)") (class "Default")
      (node (ref "U4") (pin "1") (pinfunction "Q4_1") (pintype "bidirectional"))
    )
    (net (code "65") (name "unconnected-(U4-Q5-Pad5)") (class "Default")
      (node (ref "U4") (pin "5") (pinfunction "Q5_5") (pintype "bidirectional"))
    )
    (net (code "66") (name "unconnected-(U4-Q6-Pad2)") (class "Default")
      (node (ref "U4") (pin "2") (pinfunction "Q6_2") (pintype "bidirectional"))
    )
    (net (code "67") (name "unconnected-(U4-Q7-Pad4)") (class "Default")
      (node (ref "U4") (pin "4") (pinfunction "Q7_4") (pintype "bidirectional"))
    )
    (net (code "68") (name "unconnected-(U5A-~{Q}-Pad3)") (class "Default")
      (node (ref "U5") (pin "3") (pinfunction "~{Q}_3") (pintype "output"))
    )
    (net (code "69") (name "unconnected-(U5B-~{Q}-Pad6)") (class "Default")
      (node (ref "U5") (pin "6") (pinfunction "~{Q}_6") (pintype "output"))
    )
    (net (code "70") (name "unconnected-(U5C-~{Q}-Pad11)") (class "Default")
      (node (ref "U5") (pin "11") (pinfunction "~{Q}_11") (pintype "output"))
    )
    (net (code "71") (name "unconnected-(U5D-~{Q}-Pad14)") (class "Default")
      (node (ref "U5") (pin "14") (pinfunction "~{Q}_14") (pintype "output"))
    )
  )
)
